# SAMC21_Xplained_Pro_dual_input_power_sup.net
KiCad netlist of a schematic drawn in Altium Designer
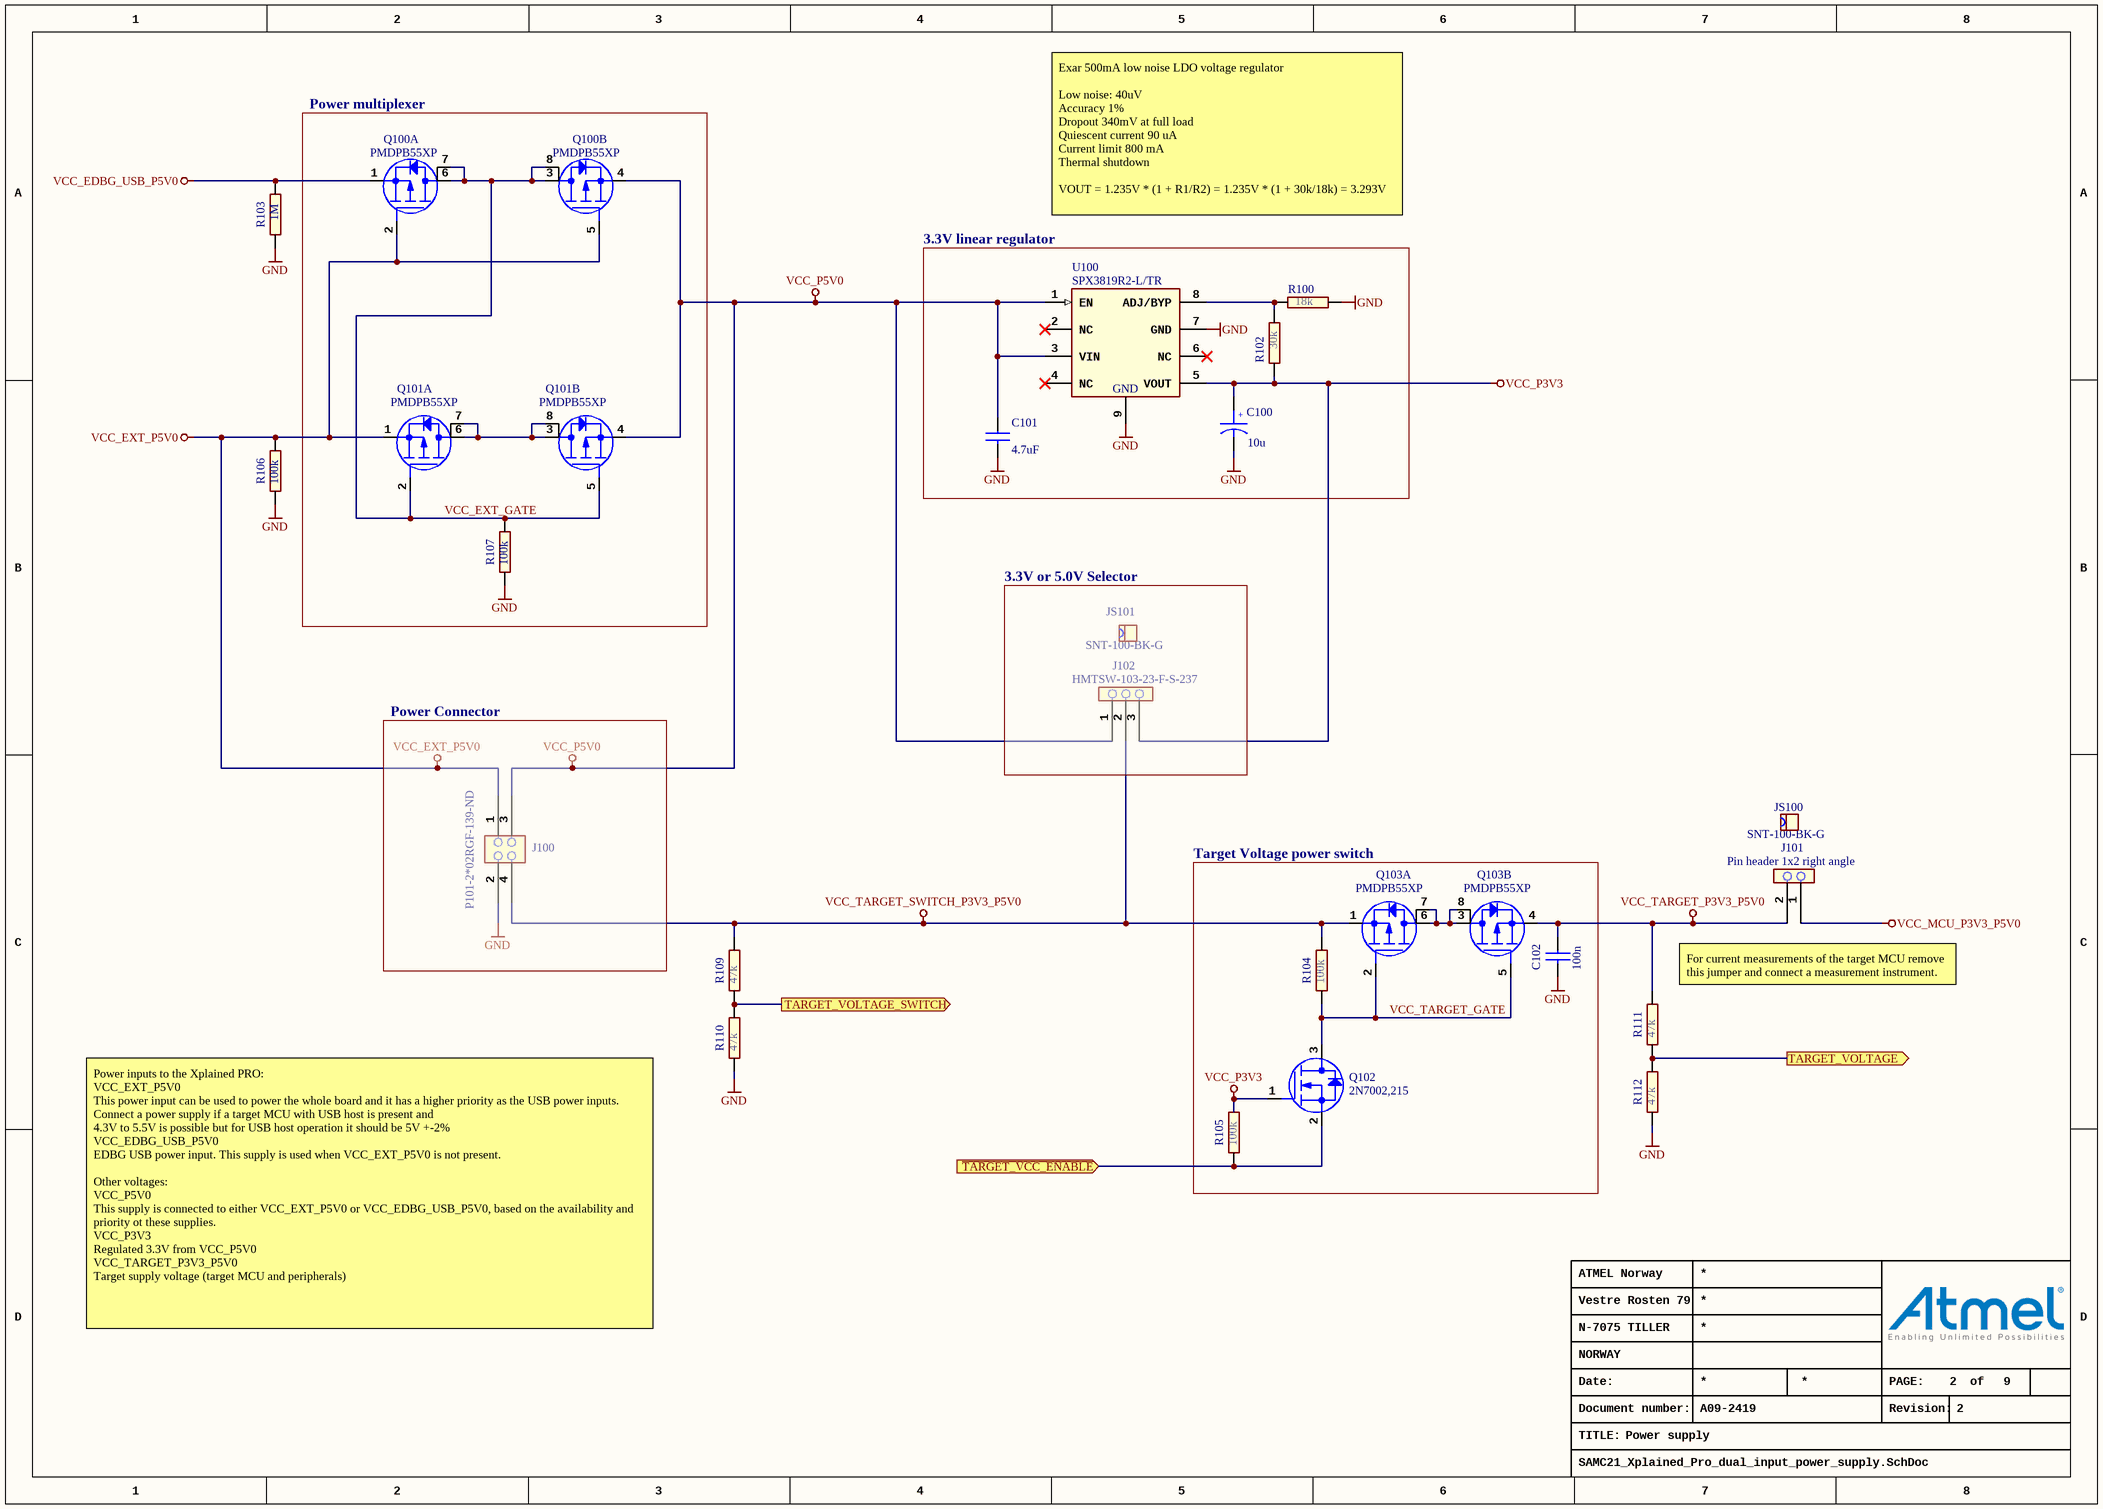
[diagram p0: SAMC21_Xplained_Pro_dual_input_power_supply.SchDoc]

(export (version "E")
  (design (tool "Eeschema 10.0.6"))
  (components
    (comp (ref "C100")
      (value "10u")
      (footprint "AP1-00036")
      (description "SMD tantalum capacitor, ESR = 1.7, 3216-18 (EIA) 1206,")
      (fields (field (name "TOLERANCE") "+-10%") (field (name "MANUFACTURER") "vishay"))
      (libsource (lib "AltiumDbLib") (part "CAP-POL"))
    )
    (comp (ref "C101")
      (value "4.7uF")
      (footprint "AP1-00039")
      (description "Ceramic capacitor, SMD 0603, X5R, 10V, 10% (de31036)")
      (fields (field (name "TOLERANCE") "10%") (field (name "MANUFACTURER") "tdk"))
      (libsource (lib "AltiumDbLib") (part "CAP-NONPOL"))
    )
    (comp (ref "C102")
      (value "100n")
      (footprint "AP1-00001")
      (description "Ceramic capacitor, SMD 0402, X7R, 16V, +/-10%")
      (fields (field (name "TOLERANCE") "16V, +/-10%") (field (name "MANUFACTURER") "Kemet"))
      (libsource (lib "AltiumDbLib") (part "CAP-NONPOL"))
    )
    (comp (ref "J100")
      (value "P101-2*02RGF-139-ND")
      (footprint "AP8-00628")
      (description "Pin header, 2x2, Right Angle, 2.54mm, THT, Pin In Paste")
      (fields (field (name "Comment") "HEADER 2x2"))
      (libsource (lib "AltiumDbLib") (part "HEADER 2x2"))
    )
    (comp (ref "J101")
      (value "Pin header 1x2 right angle")
      (footprint "AP8-00367")
      (description "1x2 pin header, right angle, 2.54 mm pitch, through-hole")
      (fields (field (name "MANUFACTURER") "Pro-data International Corp") (field (name "MPN") "2213R-2G"))
      (libsource (lib "AltiumDbLib") (part "HEADER 1x2"))
    )
    (comp (ref "J102")
      (value "HMTSW-103-23-F-S-237")
      (footprint "AP8-00745")
      (description "1x3 pin header, 2.54mm pitch, Pin-in-Paste THM, 1mm hole")
      (fields (field (name "MANUFACTURER") "SAMTEC"))
      (libsource (lib "AltiumDbLib") (part "HEADER 1x3"))
    )
    (comp (ref "JS100")
      (value "SNT-100-BK-G")
      (footprint "AP8-00525")
      (description "Jumper cap for 2.54mm pinheader")
      (fields (field (name "MANUFACTURER") "SAMTEC"))
      (libsource (lib "AltiumDbLib") (part "JUMPER_CAP"))
    )
    (comp (ref "JS101")
      (value "SNT-100-BK-G")
      (footprint "AP8-00525")
      (description "Jumper cap for 2.54mm pinheader")
      (fields (field (name "MANUFACTURER") "SAMTEC"))
      (libsource (lib "AltiumDbLib") (part "JUMPER_CAP"))
    )
    (comp (ref "Q100")
      (value "PMDPB55XP")
      (footprint "AP5-00047")
      (description "Dual P-Channel MOSFET, -20V, RDS(ON) < 55 mOhm @-3.4A@-4.5V")
      (fields (field (name "MANUFACTURER") "NXP") (field (name "Comment") "Farnell order code: 2191806"))
      (libsource (lib "AltiumDbLib") (part "MOSFET_DUAL_P_S1G1D2S2G2D1D1D2"))
    )
    (comp (ref "Q101")
      (value "PMDPB55XP")
      (footprint "AP5-00047")
      (description "Dual P-Channel MOSFET, -20V, RDS(ON) < 55 mOhm @-3.4A@-4.5V")
      (fields (field (name "MANUFACTURER") "NXP") (field (name "Comment") "Farnell order code: 2191806"))
      (libsource (lib "AltiumDbLib") (part "MOSFET_DUAL_P_S1G1D2S2G2D1D1D2"))
    )
    (comp (ref "Q102")
      (value "2N7002,215")
      (footprint "AP5-00002")
      (description "N-Channel MOSFET. 60V, 0.300A continuous, 1.2A Peak. RDS(ON) = 3.8Ohm@VGS=4.5V, VGS(th)<2.5V")
      (fields (field (name "MANUFACTURER") "NXP") (field (name "Comment") "MOSFET_N_GSD"))
      (libsource (lib "AltiumDbLib") (part "MOSFET_N_GSD"))
    )
    (comp (ref "Q103")
      (value "PMDPB55XP")
      (footprint "AP5-00047")
      (description "Dual P-Channel MOSFET, -20V, RDS(ON) < 55 mOhm @-3.4A@-4.5V")
      (fields (field (name "MANUFACTURER") "NXP") (field (name "Comment") "Farnell order code: 2191806"))
      (libsource (lib "AltiumDbLib") (part "MOSFET_DUAL_P_S1G1D2S2G2D1D1D2"))
    )
    (comp (ref "R100")
      (value "18k")
      (footprint "AP2-00000")
      (description "Thick film resistor, SMD 0402, 1/16W, 1%")
      (fields (field (name "TOLERANCE") "1 %") (field (name "Comment") "R2"))
      (libsource (lib "") (part "R2_2"))
    )
    (comp (ref "R102")
      (value "30k")
      (footprint "AP2-00000")
      (description "Thick film resistor, SMD 0402, 1/16W, 1%")
      (fields (field (name "TOLERANCE") "1 %") (field (name "Comment") "R2"))
      (libsource (lib "") (part "R2_1"))
    )
    (comp (ref "R103")
      (value "1M")
      (footprint "AP2-00000")
      (description "Thick film resistor, SMD 0402, 1/16W, 1%")
      (fields (field (name "TOLERANCE") "1 %") (field (name "Comment") "R2"))
      (libsource (lib "") (part "R2_1"))
    )
    (comp (ref "R104")
      (value "100k")
      (footprint "AP2-00000")
      (description "Thick film resistor, SMD 0402, 1/16W, 1%")
      (fields (field (name "TOLERANCE") "1 %") (field (name "Comment") "R2"))
      (libsource (lib "") (part "R2_3"))
    )
    (comp (ref "R105")
      (value "100k")
      (footprint "AP2-00000")
      (description "Thick film resistor, SMD 0402, 1/16W, 1%")
      (fields (field (name "TOLERANCE") "1 %") (field (name "Comment") "R2"))
      (libsource (lib "") (part "R2_3"))
    )
    (comp (ref "R106")
      (value "100k")
      (footprint "AP2-00000")
      (description "Thick film resistor, SMD 0402, 1/16W, 1%")
      (fields (field (name "TOLERANCE") "1 %") (field (name "Comment") "R2"))
      (libsource (lib "") (part "R2_1"))
    )
    (comp (ref "R107")
      (value "100k")
      (footprint "AP2-00000")
      (description "Thick film resistor, SMD 0402, 1/16W, 1%")
      (fields (field (name "TOLERANCE") "1 %") (field (name "Comment") "R2"))
      (libsource (lib "") (part "R2_1"))
    )
    (comp (ref "R109")
      (value "47k")
      (footprint "AP2-00000")
      (description "Thick film resistor, SMD 0402, 1/16W, 1%")
      (fields (field (name "TOLERANCE") "1 %") (field (name "Comment") "R2"))
      (libsource (lib "AltiumDbLib") (part "R2"))
    )
    (comp (ref "R110")
      (value "47k")
      (footprint "AP2-00000")
      (description "Thick film resistor, SMD 0402, 1/16W, 1%")
      (fields (field (name "TOLERANCE") "1 %") (field (name "Comment") "R2"))
      (libsource (lib "AltiumDbLib") (part "R2"))
    )
    (comp (ref "R111")
      (value "47k")
      (footprint "AP2-00000")
      (description "Thick film resistor, SMD 0402, 1/16W, 1%")
      (fields (field (name "TOLERANCE") "1 %") (field (name "Comment") "R2"))
      (libsource (lib "AltiumDbLib") (part "R2"))
    )
    (comp (ref "R112")
      (value "47k")
      (footprint "AP2-00000")
      (description "Thick film resistor, SMD 0402, 1/16W, 1%")
      (fields (field (name "TOLERANCE") "1 %") (field (name "Comment") "R2"))
      (libsource (lib "AltiumDbLib") (part "R2"))
    )
    (comp (ref "U100")
      (value "SPX3819R2-L/TR")
      (footprint "AP6-00338")
      (description "500mA LDO, ADJ, low noise, 8-DFN package")
      (fields (field (name "TOLERANCE") "±1%") (field (name "MANUFACTURER") "Exar"))
      (libsource (lib "AltiumDbLib") (part "SPX3819R2-L"))
    )
  )
  (nets
    (net (code "1") (name "/TARGET_VOLTAGE") (class "Default")
      (node (ref "R111") (pin "1") (pinfunction "1_1") (pintype "passive"))
      (node (ref "R112") (pin "2") (pinfunction "2_2") (pintype "passive"))
    )
    (net (code "2") (name "/TARGET_VOLTAGE_SWITCH") (class "Default")
      (node (ref "R109") (pin "1") (pinfunction "1_1") (pintype "passive"))
      (node (ref "R110") (pin "2") (pinfunction "2_2") (pintype "passive"))
    )
    (net (code "3") (name "/VCC_EXT_GATE") (class "Default")
      (node (ref "Q100") (pin "3") (pinfunction "D2_3") (pintype "passive"))
      (node (ref "Q100") (pin "6") (pinfunction "D1_6") (pintype "passive"))
      (node (ref "Q100") (pin "7") (pinfunction "D1_PAD_7") (pintype "passive"))
      (node (ref "Q100") (pin "8") (pinfunction "D2_PAD_8") (pintype "passive"))
      (node (ref "Q101") (pin "2") (pinfunction "G1_2") (pintype "passive"))
      (node (ref "Q101") (pin "5") (pinfunction "G2_5") (pintype "passive"))
      (node (ref "R107") (pin "2") (pinfunction "2_2") (pintype "passive"))
    )
    (net (code "4") (name "/VCC_TARGET_GATE") (class "Default")
      (node (ref "Q102") (pin "3") (pinfunction "D_3") (pintype "passive"))
      (node (ref "Q103") (pin "2") (pinfunction "G1_2") (pintype "passive"))
      (node (ref "Q103") (pin "5") (pinfunction "G2_5") (pintype "passive"))
      (node (ref "R104") (pin "2") (pinfunction "2_2") (pintype "passive"))
    )
    (net (code "5") (name "/~{TARGET_VCC_ENABLE}") (class "Default")
      (node (ref "Q102") (pin "2") (pinfunction "S_2") (pintype "passive"))
      (node (ref "R105") (pin "2") (pinfunction "2_2") (pintype "passive"))
    )
    (net (code "6") (name "GND") (class "Default")
      (node (ref "C100") (pin "2") (pinfunction "2_2") (pintype "passive"))
      (node (ref "C101") (pin "2") (pinfunction "2_2") (pintype "passive"))
      (node (ref "C102") (pin "2") (pinfunction "2_2") (pintype "passive"))
      (node (ref "J100") (pin "2") (pinfunction "2_2") (pintype "passive"))
      (node (ref "R100") (pin "2") (pinfunction "2_2") (pintype "passive"))
      (node (ref "R103") (pin "1") (pinfunction "1_1") (pintype "passive"))
      (node (ref "R106") (pin "1") (pinfunction "1_1") (pintype "passive"))
      (node (ref "R107") (pin "1") (pinfunction "1_1") (pintype "passive"))
      (node (ref "R110") (pin "1") (pinfunction "1_1") (pintype "passive"))
      (node (ref "R112") (pin "1") (pinfunction "1_1") (pintype "passive"))
      (node (ref "U100") (pin "7") (pinfunction "GND_7") (pintype "power_in"))
      (node (ref "U100") (pin "9") (pinfunction "GND_9") (pintype "power_in"))
    )
    (net (code "7") (name "Net-(Q101A-D1)") (class "Default")
      (node (ref "Q101") (pin "3") (pinfunction "D2_3") (pintype "passive"))
      (node (ref "Q101") (pin "6") (pinfunction "D1_6") (pintype "passive"))
      (node (ref "Q101") (pin "7") (pinfunction "D1_PAD_7") (pintype "passive"))
      (node (ref "Q101") (pin "8") (pinfunction "D2_PAD_8") (pintype "passive"))
    )
    (net (code "8") (name "Net-(Q103A-D1)") (class "Default")
      (node (ref "Q103") (pin "3") (pinfunction "D2_3") (pintype "passive"))
      (node (ref "Q103") (pin "6") (pinfunction "D1_6") (pintype "passive"))
      (node (ref "Q103") (pin "7") (pinfunction "D1_PAD_7") (pintype "passive"))
      (node (ref "Q103") (pin "8") (pinfunction "D2_PAD_8") (pintype "passive"))
    )
    (net (code "9") (name "Net-(U100-ADJ{slash}BYP)") (class "Default")
      (node (ref "R100") (pin "1") (pinfunction "1_1") (pintype "passive"))
      (node (ref "R102") (pin "2") (pinfunction "2_2") (pintype "passive"))
      (node (ref "U100") (pin "8") (pinfunction "ADJ/BYP_8") (pintype "passive"))
    )
    (net (code "10") (name "VCC_EDBG_USB_P5V0") (class "Default")
      (node (ref "Q100") (pin "1") (pinfunction "S1_1") (pintype "passive"))
      (node (ref "R103") (pin "2") (pinfunction "2_2") (pintype "passive"))
    )
    (net (code "11") (name "VCC_EXT_P5V0") (class "Default")
      (node (ref "J100") (pin "1") (pinfunction "1_1") (pintype "passive"))
      (node (ref "Q100") (pin "2") (pinfunction "G1_2") (pintype "passive"))
      (node (ref "Q100") (pin "5") (pinfunction "G2_5") (pintype "passive"))
      (node (ref "Q101") (pin "1") (pinfunction "S1_1") (pintype "passive"))
      (node (ref "R106") (pin "2") (pinfunction "2_2") (pintype "passive"))
    )
    (net (code "12") (name "VCC_MCU_P3V3_P5V0") (class "Default")
      (node (ref "J101") (pin "1") (pinfunction "1_1") (pintype "passive"))
    )
    (net (code "13") (name "VCC_P3V3") (class "Default")
      (node (ref "C100") (pin "1") (pinfunction "1_1") (pintype "passive"))
      (node (ref "J102") (pin "3") (pinfunction "3_3") (pintype "passive"))
      (node (ref "Q102") (pin "1") (pinfunction "G_1") (pintype "passive"))
      (node (ref "R102") (pin "1") (pinfunction "1_1") (pintype "passive"))
      (node (ref "R105") (pin "1") (pinfunction "1_1") (pintype "passive"))
      (node (ref "U100") (pin "5") (pinfunction "VOUT_5") (pintype "power_in"))
    )
    (net (code "14") (name "VCC_P5V0") (class "Default")
      (node (ref "C101") (pin "1") (pinfunction "1_1") (pintype "passive"))
      (node (ref "J100") (pin "3") (pinfunction "3_3") (pintype "passive"))
      (node (ref "J102") (pin "1") (pinfunction "1_1") (pintype "passive"))
      (node (ref "Q100") (pin "4") (pinfunction "S2_4") (pintype "passive"))
      (node (ref "Q101") (pin "4") (pinfunction "S2_4") (pintype "passive"))
      (node (ref "U100") (pin "1") (pinfunction "EN_1") (pintype "input"))
      (node (ref "U100") (pin "3") (pinfunction "VIN_3") (pintype "power_in"))
    )
    (net (code "15") (name "VCC_TARGET_P3V3_P5V0") (class "Default")
      (node (ref "C102") (pin "1") (pinfunction "1_1") (pintype "passive"))
      (node (ref "J101") (pin "2") (pinfunction "2_2") (pintype "passive"))
      (node (ref "Q103") (pin "4") (pinfunction "S2_4") (pintype "passive"))
      (node (ref "R111") (pin "2") (pinfunction "2_2") (pintype "passive"))
    )
    (net (code "16") (name "VCC_TARGET_SWITCH_P3V3_P5V0") (class "Default")
      (node (ref "J100") (pin "4") (pinfunction "4_4") (pintype "passive"))
      (node (ref "J102") (pin "2") (pinfunction "2_2") (pintype "passive"))
      (node (ref "Q103") (pin "1") (pinfunction "S1_1") (pintype "passive"))
      (node (ref "R104") (pin "1") (pinfunction "1_1") (pintype "passive"))
      (node (ref "R109") (pin "2") (pinfunction "2_2") (pintype "passive"))
    )
    (net (code "17") (name "unconnected-(U100-NC-Pad2)") (class "Default")
      (node (ref "U100") (pin "2") (pinfunction "NC_2") (pintype "passive+no_connect"))
    )
    (net (code "18") (name "unconnected-(U100-NC-Pad4)") (class "Default")
      (node (ref "U100") (pin "4") (pinfunction "NC_4") (pintype "passive+no_connect"))
    )
    (net (code "19") (name "unconnected-(U100-NC-Pad6)") (class "Default")
      (node (ref "U100") (pin "6") (pinfunction "NC_6") (pintype "passive+no_connect"))
    )
  )
)
